# MCU_STM32F446RE.net
KiCad netlist of a schematic drawn in Altium Designer
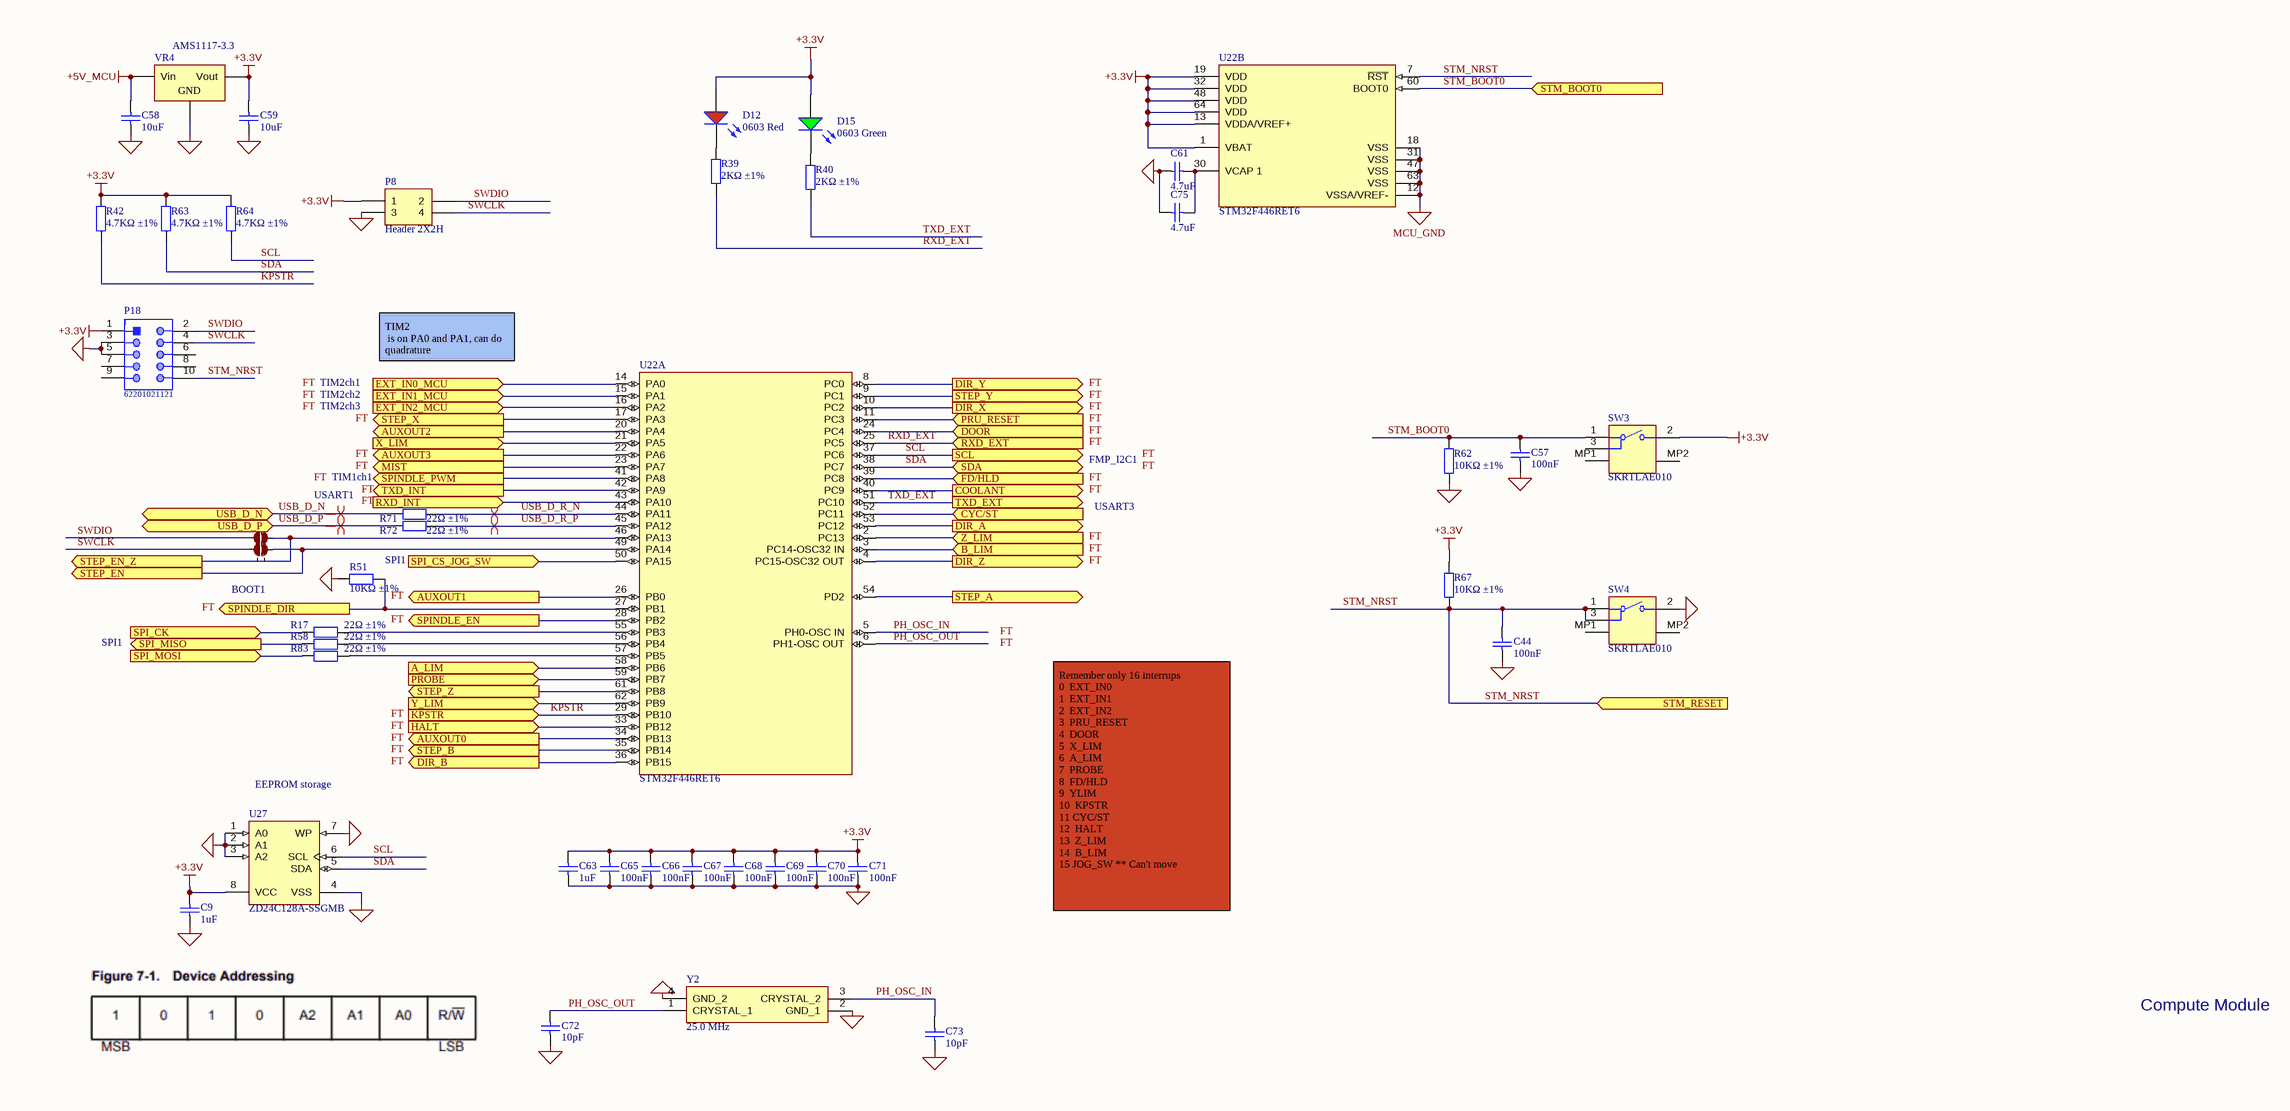
[diagram p0: MCU_STM32F446RE.SchDoc]

(export (version "E")
  (design (tool "Eeschema 10.0.6"))
  (components
    (comp (ref "C9")
      (value "1uF")
      (footprint "0603_C")
      (description "Chip capacitors")
      (fields
        (field (name "MANUFACTURER") "Samsung Electro-Mechanics")
        (field (name "PARTNUMBER") "CL10A105KB8NNNC")
      )
      (libsource (lib "Cap") (part "0603 1uF (105) 10% 50V"))
    )
    (comp (ref "C44")
      (value "100nF")
      (footprint "0603_C")
      (description "Chip capacitors")
      (fields (field (name "MANUFACTURER") "YAGEO") (field (name "PARTNUMBER") "CC0603KRX7R9BB104"))
      (libsource (lib "Cap") (part "0603 100nF (104) 10% 50V"))
    )
    (comp (ref "C57")
      (value "100nF")
      (footprint "0603_C")
      (description "Chip capacitors")
      (fields (field (name "MANUFACTURER") "YAGEO") (field (name "PARTNUMBER") "CC0603KRX7R9BB104"))
      (libsource (lib "Cap") (part "0603 100nF (104) 10% 50V"))
    )
    (comp (ref "C58")
      (value "10uF")
      (footprint "1206_C")
      (description "Chip capacitors")
      (fields
        (field (name "MANUFACTURER") "Samsung Electro-Mechanics")
        (field (name "PARTNUMBER") "CL31A106KBHNNNE")
      )
      (libsource (lib "Cap") (part "1206 10uF (106) 10% 50V"))
    )
    (comp (ref "C59")
      (value "10uF")
      (footprint "1206_C")
      (description "Chip capacitors")
      (fields
        (field (name "MANUFACTURER") "Samsung Electro-Mechanics")
        (field (name "PARTNUMBER") "CL31A106KBHNNNE")
      )
      (libsource (lib "Cap") (part "1206 10uF (106) 10% 50V"))
    )
    (comp (ref "C61")
      (value "4.7uF")
      (footprint "0603_C")
      (description "Chip capacitors")
      (fields
        (field (name "MANUFACTURER") "Samsung Electro-Mechanics")
        (field (name "PARTNUMBER") "CL10A475KO8NNNC")
      )
      (libsource (lib "Cap") (part "0603 4.7uF (475) 10% 16V"))
    )
    (comp (ref "C63")
      (value "1uF")
      (footprint "0603_C")
      (description "Chip capacitors")
      (fields
        (field (name "MANUFACTURER") "Samsung Electro-Mechanics")
        (field (name "PARTNUMBER") "CL10A105KB8NNNC")
      )
      (libsource (lib "Cap") (part "0603 1uF (105) 10% 50V"))
    )
    (comp (ref "C65")
      (value "100nF")
      (footprint "0603_C")
      (description "Chip capacitors")
      (fields (field (name "MANUFACTURER") "YAGEO") (field (name "PARTNUMBER") "CC0603KRX7R9BB104"))
      (libsource (lib "Cap") (part "0603 100nF (104) 10% 50V"))
    )
    (comp (ref "C66")
      (value "100nF")
      (footprint "0603_C")
      (description "Chip capacitors")
      (fields (field (name "MANUFACTURER") "YAGEO") (field (name "PARTNUMBER") "CC0603KRX7R9BB104"))
      (libsource (lib "Cap") (part "0603 100nF (104) 10% 50V"))
    )
    (comp (ref "C67")
      (value "100nF")
      (footprint "0603_C")
      (description "Chip capacitors")
      (fields (field (name "MANUFACTURER") "YAGEO") (field (name "PARTNUMBER") "CC0603KRX7R9BB104"))
      (libsource (lib "Cap") (part "0603 100nF (104) 10% 50V"))
    )
    (comp (ref "C68")
      (value "100nF")
      (footprint "0603_C")
      (description "Chip capacitors")
      (fields (field (name "MANUFACTURER") "YAGEO") (field (name "PARTNUMBER") "CC0603KRX7R9BB104"))
      (libsource (lib "Cap") (part "0603 100nF (104) 10% 50V"))
    )
    (comp (ref "C69")
      (value "100nF")
      (footprint "0603_C")
      (description "Chip capacitors")
      (fields (field (name "MANUFACTURER") "YAGEO") (field (name "PARTNUMBER") "CC0603KRX7R9BB104"))
      (libsource (lib "Cap") (part "0603 100nF (104) 10% 50V"))
    )
    (comp (ref "C70")
      (value "100nF")
      (footprint "0603_C")
      (description "Chip capacitors")
      (fields (field (name "MANUFACTURER") "YAGEO") (field (name "PARTNUMBER") "CC0603KRX7R9BB104"))
      (libsource (lib "Cap") (part "0603 100nF (104) 10% 50V"))
    )
    (comp (ref "C71")
      (value "100nF")
      (footprint "0603_C")
      (description "Chip capacitors")
      (fields (field (name "MANUFACTURER") "YAGEO") (field (name "PARTNUMBER") "CC0603KRX7R9BB104"))
      (libsource (lib "Cap") (part "0603 100nF (104) 10% 50V"))
    )
    (comp (ref "C72")
      (value "10pF")
      (footprint "0603_C")
      (description "Chip capacitors")
      (fields
        (field (name "MANUFACTURER") "Samsung Electro-Mechanics")
        (field (name "PARTNUMBER") "CL10C100JB8NNNC")
      )
      (libsource (lib "Cap") (part "0603 10pF (100) 5% 50V"))
    )
    (comp (ref "C73")
      (value "10pF")
      (footprint "0603_C")
      (description "Chip capacitors")
      (fields
        (field (name "MANUFACTURER") "Samsung Electro-Mechanics")
        (field (name "PARTNUMBER") "CL10C100JB8NNNC")
      )
      (libsource (lib "Cap") (part "0603 10pF (100) 5% 50V"))
    )
    (comp (ref "C75")
      (value "4.7uF")
      (footprint "0603_C")
      (description "Chip capacitors")
      (fields
        (field (name "MANUFACTURER") "Samsung Electro-Mechanics")
        (field (name "PARTNUMBER") "CL10A475KO8NNNC")
      )
      (libsource (lib "Cap") (part "0603 4.7uF (475) 10% 16V"))
    )
    (comp (ref "D12")
      (value "0603 Red")
      (footprint "0603_LED_S1")
      (description "LED")
      (libsource (lib "LED") (part "0603 LED Red"))
    )
    (comp (ref "D15")
      (value "0603 Green")
      (footprint "0603_LED_S1")
      (description "LED")
      (libsource (lib "LED") (part "0603 LED Green"))
    )
    (comp (ref "J10")
      (value "2 way net solder junction - Normally Open")
      (footprint "2waySolder_NO")
      (libsource (lib "PrintNC_GRBLHAL_Breakout") (part "2waySolderNO"))
    )
    (comp (ref "J11")
      (value "2 way net solder junction - Normally Open")
      (footprint "2waySolder_NO")
      (libsource (lib "PrintNC_GRBLHAL_Breakout") (part "2waySolderNO"))
    )
    (comp (ref "P8")
      (value "Header 2X2H")
      (footprint "HDR2X2H")
      (description "Header, 2-Pin, Dual row, Right Angle")
      (fields (field (name "PUBLISHER") "Altium Limited"))
      (libsource (lib "Miscellaneous Connectors") (part "Header 2X2H"))
    )
    (comp (ref "P18")
      (value "62201021121")
      (footprint "62201021121")
      (description "THT Vertical Pin Header WR-PHD, Pitch 1.27 mm, Dual Row, 10 pins")
      (fields (field (name "MANUFACTURER") "Wurth Elektronik") (field (name "PUBLISHER") "WurthElektronik"))
      (libsource (lib "Altium Content Vault") (part "WE-CN-2P-M-R10"))
    )
    (comp (ref "R17")
      (value "22Ω ±1%")
      (footprint "0603_R")
      (description "Chip resistor")
      (fields (field (name "MANUFACTURER") "Uniroyal Elec") (field (name "PARTNUMBER") "0603WAF220JT5E"))
      (libsource (lib "RES") (part "0603 22R (22R0) 1%"))
    )
    (comp (ref "R39")
      (value "2KΩ ±1%")
      (footprint "0603_R")
      (description "Chip resistor")
      (fields (field (name "MANUFACTURER") "Uniroyal Elec") (field (name "PARTNUMBER") "0603WAF2001T5E"))
      (libsource (lib "RES") (part "0603 2K (2001) 1%"))
    )
    (comp (ref "R40")
      (value "2KΩ ±1%")
      (footprint "0603_R")
      (description "Chip resistor")
      (fields (field (name "MANUFACTURER") "Uniroyal Elec") (field (name "PARTNUMBER") "0603WAF2001T5E"))
      (libsource (lib "RES") (part "0603 2K (2001) 1%"))
    )
    (comp (ref "R42")
      (value "4.7KΩ ±1%")
      (footprint "0603_R")
      (description "Chip resistor")
      (fields (field (name "MANUFACTURER") "Uniroyal Elec") (field (name "PARTNUMBER") "0603WAF4701T5E"))
      (libsource (lib "RES") (part "0603 4.7K (4701) 1%"))
    )
    (comp (ref "R51")
      (value "10KΩ ±1%")
      (footprint "0603_R")
      (description "Chip resistor")
      (fields (field (name "MANUFACTURER") "Uniroyal Elec") (field (name "PARTNUMBER") "0603WAF1002T5E"))
      (libsource (lib "RES") (part "0603 10K (1002) 1%"))
    )
    (comp (ref "R58")
      (value "22Ω ±1%")
      (footprint "0603_R")
      (description "Chip resistor")
      (fields (field (name "MANUFACTURER") "Uniroyal Elec") (field (name "PARTNUMBER") "0603WAF220JT5E"))
      (libsource (lib "RES") (part "0603 22R (22R0) 1%"))
    )
    (comp (ref "R62")
      (value "10KΩ ±1%")
      (footprint "0603_R")
      (description "Chip resistor")
      (fields (field (name "MANUFACTURER") "Uniroyal Elec") (field (name "PARTNUMBER") "0603WAF1002T5E"))
      (libsource (lib "") (part "0603 10K (1002) 1%_1"))
    )
    (comp (ref "R63")
      (value "4.7KΩ ±1%")
      (footprint "0603_R")
      (description "Chip resistor")
      (fields (field (name "MANUFACTURER") "Uniroyal Elec") (field (name "PARTNUMBER") "0603WAF4701T5E"))
      (libsource (lib "RES") (part "0603 4.7K (4701) 1%"))
    )
    (comp (ref "R64")
      (value "4.7KΩ ±1%")
      (footprint "0603_R")
      (description "Chip resistor")
      (fields (field (name "MANUFACTURER") "Uniroyal Elec") (field (name "PARTNUMBER") "0603WAF4701T5E"))
      (libsource (lib "RES") (part "0603 4.7K (4701) 1%"))
    )
    (comp (ref "R67")
      (value "10KΩ ±1%")
      (footprint "0603_R")
      (description "Chip resistor")
      (fields (field (name "MANUFACTURER") "Uniroyal Elec") (field (name "PARTNUMBER") "0603WAF1002T5E"))
      (libsource (lib "") (part "0603 10K (1002) 1%_1"))
    )
    (comp (ref "R71")
      (value "22Ω ±1%")
      (footprint "0603_R")
      (description "Chip resistor")
      (fields (field (name "MANUFACTURER") "Uniroyal Elec") (field (name "PARTNUMBER") "0603WAF220JT5E"))
      (libsource (lib "RES") (part "0603 22R (22R0) 1%"))
    )
    (comp (ref "R72")
      (value "22Ω ±1%")
      (footprint "0603_R")
      (description "Chip resistor")
      (fields (field (name "MANUFACTURER") "Uniroyal Elec") (field (name "PARTNUMBER") "0603WAF220JT5E"))
      (libsource (lib "RES") (part "0603 22R (22R0) 1%"))
    )
    (comp (ref "R83")
      (value "22Ω ±1%")
      (footprint "0603_R")
      (description "Chip resistor")
      (fields (field (name "MANUFACTURER") "Uniroyal Elec") (field (name "PARTNUMBER") "0603WAF220JT5E"))
      (libsource (lib "RES") (part "0603 22R (22R0) 1%"))
    )
    (comp (ref "SW3")
      (value "SKRTLAE010")
      (footprint "ALPS-SKRTLAE010_V")
      (description "Side Push Type, 250 V, -40 to 90 degC, 3-Pin SMD, RoHS, Tape and Reel")
      (fields (field (name "MANUFACTURER") "ALPS"))
      (libsource (lib "Altium Content Vault") (part "SW_SPST-3_A"))
    )
    (comp (ref "SW4")
      (value "SKRTLAE010")
      (footprint "ALPS-SKRTLAE010_V")
      (description "Side Push Type, 250 V, -40 to 90 degC, 3-Pin SMD, RoHS, Tape and Reel")
      (fields (field (name "MANUFACTURER") "ALPS"))
      (libsource (lib "Altium Content Vault") (part "SW_SPST-3_A"))
    )
    (comp (ref "U22")
      (value "STM32F446RET6")
      (footprint "FP-LQFP64-5W-IPC_B")
      (description "IC MCU 32BIT 512KB FLASH 64LQFP")
      (fields
        (field (name "OCTOPART") "https://octopart.com/stm32f446ret6-stmicroelectronics-52642920")
        (field (name "MANUFACTURER") "STMicroelectronics")
      )
      (libsource (lib "Universal_CNC_Breakout") (part "STM32F446RET6"))
    )
    (comp (ref "U27")
      (value "ZD24C128A-SSGMB")
      (footprint "SOIC-SN8_L")
      (description "IC EEPROM 128KBIT I2C 8SOIC")
      (libsource (lib "PrintNC_GRBLHAL_Breakout") (part "MEM-SEEPROM-34AA02-IL8"))
    )
    (comp (ref "VR4")
      (value "AMS1117-3.3")
      (footprint "SOT-223")
      (description "Vout=3.3V 1A 72dB@(120Hz) (LDO)")
      (libsource (lib "LDO") (part "SOT-223 AMS1117-3.3"))
    )
    (comp (ref "Y2")
      (value "25.0 MHz")
      (footprint "SamacSys:YSX321SL")
      (description "Crystal or Oscillator")
      (fields (field (name "MANUFACTURER_PART_NUMBER") "X322525MSB4SI"))
      (libsource (lib "*") (part "YSX321SL"))
    )
  )
  (nets
    (net (code "1") (name "+3.3V") (class "Default")
      (node (ref "C59") (pin "2") (pinfunction "2_2") (pintype "passive"))
      (node (ref "C63") (pin "2") (pinfunction "2_2") (pintype "passive"))
      (node (ref "C65") (pin "2") (pinfunction "2_2") (pintype "passive"))
      (node (ref "C66") (pin "2") (pinfunction "2_2") (pintype "passive"))
      (node (ref "C67") (pin "2") (pinfunction "2_2") (pintype "passive"))
      (node (ref "C68") (pin "2") (pinfunction "2_2") (pintype "passive"))
      (node (ref "C69") (pin "2") (pinfunction "2_2") (pintype "passive"))
      (node (ref "C70") (pin "2") (pinfunction "2_2") (pintype "passive"))
      (node (ref "C71") (pin "2") (pinfunction "2_2") (pintype "passive"))
      (node (ref "C9") (pin "2") (pinfunction "2_2") (pintype "passive"))
      (node (ref "D12") (pin "A") (pinfunction "A_A") (pintype "passive"))
      (node (ref "D15") (pin "A") (pinfunction "A_A") (pintype "passive"))
      (node (ref "P18") (pin "1") (pinfunction "1_1") (pintype "passive"))
      (node (ref "P8") (pin "1") (pinfunction "1_1") (pintype "passive"))
      (node (ref "R42") (pin "2") (pinfunction "2_2") (pintype "passive"))
      (node (ref "R63") (pin "2") (pinfunction "2_2") (pintype "passive"))
      (node (ref "R64") (pin "2") (pinfunction "2_2") (pintype "passive"))
      (node (ref "R67") (pin "1") (pinfunction "1_1") (pintype "passive"))
      (node (ref "SW3") (pin "2") (pinfunction "2_2") (pintype "passive"))
      (node (ref "U22") (pin "1") (pinfunction "VBAT_1") (pintype "power_in"))
      (node (ref "U22") (pin "13") (pinfunction "VDDA/VREF+_13") (pintype "power_in"))
      (node (ref "U22") (pin "19") (pinfunction "VDD_19") (pintype "power_in"))
      (node (ref "U22") (pin "32") (pinfunction "VDD_32") (pintype "power_in"))
      (node (ref "U22") (pin "48") (pinfunction "VDD_48") (pintype "power_in"))
      (node (ref "U22") (pin "64") (pinfunction "VDD_64") (pintype "power_in"))
      (node (ref "U27") (pin "8") (pinfunction "VCC_8") (pintype "power_in"))
      (node (ref "VR4") (pin "2") (pinfunction "Vout_2") (pintype "passive"))
    )
    (net (code "2") (name "+5V_MCU") (class "Default")
      (node (ref "C58") (pin "2") (pinfunction "2_2") (pintype "passive"))
      (node (ref "VR4") (pin "3") (pinfunction "Vin_3") (pintype "passive"))
    )
    (net (code "3") (name "/AUXOUT0") (class "Default")
      (node (ref "U22") (pin "34") (pinfunction "PB13_34") (pintype "bidirectional"))
    )
    (net (code "4") (name "/AUXOUT1") (class "Default")
      (node (ref "U22") (pin "26") (pinfunction "PB0_26") (pintype "bidirectional"))
    )
    (net (code "5") (name "/AUXOUT2") (class "Default")
      (node (ref "U22") (pin "20") (pinfunction "PA4_20") (pintype "bidirectional"))
    )
    (net (code "6") (name "/AUXOUT3") (class "Default")
      (node (ref "U22") (pin "22") (pinfunction "PA6_22") (pintype "bidirectional"))
    )
    (net (code "7") (name "/A_LIM") (class "Default")
      (node (ref "U22") (pin "58") (pinfunction "PB6_58") (pintype "bidirectional"))
    )
    (net (code "8") (name "/B_LIM") (class "Default")
      (node (ref "U22") (pin "3") (pinfunction "PC14-OSC32_IN_3") (pintype "bidirectional"))
    )
    (net (code "9") (name "/COOLANT") (class "Default")
      (node (ref "U22") (pin "40") (pinfunction "PC9_40") (pintype "bidirectional"))
    )
    (net (code "10") (name "/CYC{slash}ST") (class "Default")
      (node (ref "U22") (pin "52") (pinfunction "PC11_52") (pintype "bidirectional"))
    )
    (net (code "11") (name "/DIR_A") (class "Default")
      (node (ref "U22") (pin "53") (pinfunction "PC12_53") (pintype "bidirectional"))
    )
    (net (code "12") (name "/DIR_B") (class "Default")
      (node (ref "U22") (pin "36") (pinfunction "PB15_36") (pintype "bidirectional"))
    )
    (net (code "13") (name "/DIR_X") (class "Default")
      (node (ref "U22") (pin "10") (pinfunction "PC2_10") (pintype "bidirectional"))
    )
    (net (code "14") (name "/DIR_Y") (class "Default")
      (node (ref "U22") (pin "8") (pinfunction "PC0_8") (pintype "bidirectional"))
    )
    (net (code "15") (name "/DIR_Z") (class "Default")
      (node (ref "U22") (pin "4") (pinfunction "PC15-OSC32_OUT_4") (pintype "bidirectional"))
    )
    (net (code "16") (name "/DOOR") (class "Default")
      (node (ref "U22") (pin "24") (pinfunction "PC4_24") (pintype "bidirectional"))
    )
    (net (code "17") (name "/EXT_IN0_MCU") (class "Default")
      (node (ref "U22") (pin "14") (pinfunction "PA0_14") (pintype "bidirectional"))
    )
    (net (code "18") (name "/EXT_IN1_MCU") (class "Default")
      (node (ref "U22") (pin "15") (pinfunction "PA1_15") (pintype "bidirectional"))
    )
    (net (code "19") (name "/EXT_IN2_MCU") (class "Default")
      (node (ref "U22") (pin "16") (pinfunction "PA2_16") (pintype "bidirectional"))
    )
    (net (code "20") (name "/FD{slash}HLD") (class "Default")
      (node (ref "U22") (pin "39") (pinfunction "PC8_39") (pintype "bidirectional"))
    )
    (net (code "21") (name "/HALT") (class "Default")
      (node (ref "U22") (pin "33") (pinfunction "PB12_33") (pintype "bidirectional"))
    )
    (net (code "22") (name "/KPSTR") (class "Default")
      (node (ref "R42") (pin "1") (pinfunction "1_1") (pintype "passive"))
      (node (ref "U22") (pin "29") (pinfunction "PB10_29") (pintype "bidirectional"))
    )
    (net (code "23") (name "/MIST") (class "Default")
      (node (ref "U22") (pin "23") (pinfunction "PA7_23") (pintype "bidirectional"))
    )
    (net (code "24") (name "/PH_OSC_IN") (class "Default")
      (node (ref "C73") (pin "2") (pinfunction "2_2") (pintype "passive"))
      (node (ref "U22") (pin "5") (pinfunction "PH0-OSC_IN_5") (pintype "bidirectional"))
      (node (ref "Y2") (pin "3") (pinfunction "CRYSTAL_2_3") (pintype "passive"))
    )
    (net (code "25") (name "/PH_OSC_OUT") (class "Default")
      (node (ref "C72") (pin "2") (pinfunction "2_2") (pintype "passive"))
      (node (ref "U22") (pin "6") (pinfunction "PH1-OSC_OUT_6") (pintype "bidirectional"))
      (node (ref "Y2") (pin "1") (pinfunction "CRYSTAL_1_1") (pintype "passive"))
    )
    (net (code "26") (name "/PROBE") (class "Default")
      (node (ref "U22") (pin "59") (pinfunction "PB7_59") (pintype "bidirectional"))
    )
    (net (code "27") (name "/PRU_RESET") (class "Default")
      (node (ref "U22") (pin "11") (pinfunction "PC3_11") (pintype "bidirectional"))
    )
    (net (code "28") (name "/RXD_EXT") (class "Default")
      (node (ref "R39") (pin "1") (pinfunction "1_1") (pintype "passive"))
      (node (ref "U22") (pin "25") (pinfunction "PC5_25") (pintype "bidirectional"))
    )
    (net (code "29") (name "/RXD_INT") (class "Default")
      (node (ref "U22") (pin "43") (pinfunction "PA10_43") (pintype "bidirectional"))
    )
    (net (code "30") (name "/SCL") (class "Default")
      (node (ref "R64") (pin "1") (pinfunction "1_1") (pintype "passive"))
      (node (ref "U22") (pin "37") (pinfunction "PC6_37") (pintype "bidirectional"))
      (node (ref "U27") (pin "6") (pinfunction "SCL_6") (pintype "input"))
    )
    (net (code "31") (name "/SDA") (class "Default")
      (node (ref "R63") (pin "1") (pinfunction "1_1") (pintype "passive"))
      (node (ref "U22") (pin "38") (pinfunction "PC7_38") (pintype "bidirectional"))
      (node (ref "U27") (pin "5") (pinfunction "SDA_5") (pintype "bidirectional"))
    )
    (net (code "32") (name "/SPINDLE_DIR") (class "Default")
      (node (ref "R51") (pin "2") (pinfunction "2_2") (pintype "passive"))
      (node (ref "U22") (pin "27") (pinfunction "PB1_27") (pintype "bidirectional"))
    )
    (net (code "33") (name "/SPINDLE_EN") (class "Default")
      (node (ref "U22") (pin "28") (pinfunction "PB2_28") (pintype "bidirectional"))
    )
    (net (code "34") (name "/SPINDLE_PWM") (class "Default")
      (node (ref "U22") (pin "41") (pinfunction "PA8_41") (pintype "bidirectional"))
    )
    (net (code "35") (name "/SPI_CK") (class "Default")
      (node (ref "R17") (pin "2") (pinfunction "2_2") (pintype "passive"))
    )
    (net (code "36") (name "/SPI_CS_JOG_SW") (class "Default")
      (node (ref "U22") (pin "50") (pinfunction "PA15_50") (pintype "bidirectional"))
    )
    (net (code "37") (name "/SPI_MISO") (class "Default")
      (node (ref "R58") (pin "2") (pinfunction "2_2") (pintype "passive"))
    )
    (net (code "38") (name "/SPI_MOSI") (class "Default")
      (node (ref "R83") (pin "2") (pinfunction "2_2") (pintype "passive"))
    )
    (net (code "39") (name "/STEP_A") (class "Default")
      (node (ref "U22") (pin "54") (pinfunction "PD2_54") (pintype "bidirectional"))
    )
    (net (code "40") (name "/STEP_B") (class "Default")
      (node (ref "U22") (pin "35") (pinfunction "PB14_35") (pintype "bidirectional"))
    )
    (net (code "41") (name "/STEP_EN") (class "Default")
      (node (ref "J11") (pin "2") (pinfunction "2_2") (pintype "passive"))
      (node (ref "U22") (pin "49") (pinfunction "PA14_49") (pintype "bidirectional"))
    )
    (net (code "42") (name "/STEP_EN_Z") (class "Default")
      (node (ref "J10") (pin "2") (pinfunction "2_2") (pintype "passive"))
      (node (ref "U22") (pin "46") (pinfunction "PA13_46") (pintype "bidirectional"))
    )
    (net (code "43") (name "/STEP_X") (class "Default")
      (node (ref "U22") (pin "17") (pinfunction "PA3_17") (pintype "bidirectional"))
    )
    (net (code "44") (name "/STEP_Y") (class "Default")
      (node (ref "U22") (pin "9") (pinfunction "PC1_9") (pintype "bidirectional"))
    )
    (net (code "45") (name "/STEP_Z") (class "Default")
      (node (ref "U22") (pin "61") (pinfunction "PB8_61") (pintype "bidirectional"))
    )
    (net (code "46") (name "/STM_BOOT0") (class "Default")
      (node (ref "C57") (pin "2") (pinfunction "2_2") (pintype "passive"))
      (node (ref "R62") (pin "1") (pinfunction "1_1") (pintype "passive"))
      (node (ref "SW3") (pin "1") (pinfunction "1_1") (pintype "passive"))
      (node (ref "U22") (pin "60") (pinfunction "BOOT0_60") (pintype "input"))
    )
    (net (code "47") (name "/STM_NRST") (class "Default")
      (node (ref "C44") (pin "2") (pinfunction "2_2") (pintype "passive"))
      (node (ref "P18") (pin "10") (pinfunction "10_10") (pintype "passive"))
      (node (ref "R67") (pin "2") (pinfunction "2_2") (pintype "passive"))
      (node (ref "SW4") (pin "1") (pinfunction "1_1") (pintype "passive"))
      (node (ref "SW4") (pin "3") (pinfunction "3_3") (pintype "passive"))
      (node (ref "U22") (pin "7") (pinfunction "~{RST}_7") (pintype "input"))
    )
    (net (code "48") (name "/SWCLK") (class "Default")
      (node (ref "J11") (pin "1") (pinfunction "1_1") (pintype "passive"))
      (node (ref "P18") (pin "4") (pinfunction "4_4") (pintype "passive"))
      (node (ref "P8") (pin "4") (pinfunction "4_4") (pintype "passive"))
    )
    (net (code "49") (name "/SWDIO") (class "Default")
      (node (ref "J10") (pin "1") (pinfunction "1_1") (pintype "passive"))
      (node (ref "P18") (pin "2") (pinfunction "2_2") (pintype "passive"))
      (node (ref "P8") (pin "2") (pinfunction "2_2") (pintype "passive"))
    )
    (net (code "50") (name "/TXD_EXT") (class "Default")
      (node (ref "R40") (pin "1") (pinfunction "1_1") (pintype "passive"))
      (node (ref "U22") (pin "51") (pinfunction "PC10_51") (pintype "bidirectional"))
    )
    (net (code "51") (name "/TXD_INT") (class "Default")
      (node (ref "U22") (pin "42") (pinfunction "PA9_42") (pintype "bidirectional"))
    )
    (net (code "52") (name "/USB_D_N") (class "Default")
      (node (ref "R71") (pin "2") (pinfunction "2_2") (pintype "passive"))
    )
    (net (code "53") (name "/USB_D_P") (class "Default")
      (node (ref "R72") (pin "2") (pinfunction "2_2") (pintype "passive"))
    )
    (net (code "54") (name "/USB_D_R_N") (class "Default")
      (node (ref "R71") (pin "1") (pinfunction "1_1") (pintype "passive"))
      (node (ref "U22") (pin "44") (pinfunction "PA11_44") (pintype "bidirectional"))
    )
    (net (code "55") (name "/USB_D_R_P") (class "Default")
      (node (ref "R72") (pin "1") (pinfunction "1_1") (pintype "passive"))
      (node (ref "U22") (pin "45") (pinfunction "PA12_45") (pintype "bidirectional"))
    )
    (net (code "56") (name "/X_LIM") (class "Default")
      (node (ref "U22") (pin "21") (pinfunction "PA5_21") (pintype "bidirectional"))
    )
    (net (code "57") (name "/Y_LIM") (class "Default")
      (node (ref "U22") (pin "62") (pinfunction "PB9_62") (pintype "bidirectional"))
    )
    (net (code "58") (name "/Z_LIM") (class "Default")
      (node (ref "U22") (pin "2") (pinfunction "PC13_2") (pintype "bidirectional"))
    )
    (net (code "59") (name "MCU_GND") (class "Default")
      (node (ref "C44") (pin "1") (pinfunction "1_1") (pintype "passive"))
      (node (ref "C57") (pin "1") (pinfunction "1_1") (pintype "passive"))
      (node (ref "C58") (pin "1") (pinfunction "1_1") (pintype "passive"))
      (node (ref "C59") (pin "1") (pinfunction "1_1") (pintype "passive"))
      (node (ref "C61") (pin "1") (pinfunction "1_1") (pintype "passive"))
      (node (ref "C63") (pin "1") (pinfunction "1_1") (pintype "passive"))
      (node (ref "C65") (pin "1") (pinfunction "1_1") (pintype "passive"))
      (node (ref "C66") (pin "1") (pinfunction "1_1") (pintype "passive"))
      (node (ref "C67") (pin "1") (pinfunction "1_1") (pintype "passive"))
      (node (ref "C68") (pin "1") (pinfunction "1_1") (pintype "passive"))
      (node (ref "C69") (pin "1") (pinfunction "1_1") (pintype "passive"))
      (node (ref "C70") (pin "1") (pinfunction "1_1") (pintype "passive"))
      (node (ref "C71") (pin "1") (pinfunction "1_1") (pintype "passive"))
      (node (ref "C72") (pin "1") (pinfunction "1_1") (pintype "passive"))
      (node (ref "C73") (pin "1") (pinfunction "1_1") (pintype "passive"))
      (node (ref "C75") (pin "1") (pinfunction "1_1") (pintype "passive"))
      (node (ref "C9") (pin "1") (pinfunction "1_1") (pintype "passive"))
      (node (ref "P18") (pin "3") (pinfunction "3_3") (pintype "passive"))
      (node (ref "P18") (pin "5") (pinfunction "5_5") (pintype "passive"))
      (node (ref "P8") (pin "3") (pinfunction "3_3") (pintype "passive"))
      (node (ref "R51") (pin "1") (pinfunction "1_1") (pintype "passive"))
      (node (ref "R62") (pin "2") (pinfunction "2_2") (pintype "passive"))
      (node (ref "SW4") (pin "2") (pinfunction "2_2") (pintype "passive"))
      (node (ref "U22") (pin "12") (pinfunction "VSSA/VREF-_12") (pintype "power_in"))
      (node (ref "U22") (pin "18") (pinfunction "VSS_18") (pintype "power_in"))
      (node (ref "U22") (pin "31") (pinfunction "VSS_31") (pintype "power_in"))
      (node (ref "U22") (pin "47") (pinfunction "VSS_47") (pintype "power_in"))
      (node (ref "U22") (pin "63") (pinfunction "VSS_63") (pintype "power_in"))
      (node (ref "U27") (pin "1") (pinfunction "A0_1") (pintype "input"))
      (node (ref "U27") (pin "2") (pinfunction "A1_2") (pintype "input"))
      (node (ref "U27") (pin "3") (pinfunction "A2_3") (pintype "input"))
      (node (ref "U27") (pin "4") (pinfunction "VSS_4") (pintype "power_in"))
      (node (ref "U27") (pin "7") (pinfunction "WP_7") (pintype "input"))
      (node (ref "VR4") (pin "1") (pinfunction "GND_1") (pintype "passive"))
      (node (ref "Y2") (pin "2") (pinfunction "GND_1_2") (pintype "passive"))
      (node (ref "Y2") (pin "4") (pinfunction "GND_2_4") (pintype "passive"))
    )
    (net (code "60") (name "Net-(D12-PadK)") (class "Default")
      (node (ref "D12") (pin "K") (pinfunction "K_K") (pintype "passive"))
      (node (ref "R39") (pin "2") (pinfunction "2_2") (pintype "passive"))
    )
    (net (code "61") (name "Net-(D15-PadK)") (class "Default")
      (node (ref "D15") (pin "K") (pinfunction "K_K") (pintype "passive"))
      (node (ref "R40") (pin "2") (pinfunction "2_2") (pintype "passive"))
    )
    (net (code "62") (name "Net-(U22A-PB3)") (class "Default")
      (node (ref "R17") (pin "1") (pinfunction "1_1") (pintype "passive"))
      (node (ref "U22") (pin "55") (pinfunction "PB3_55") (pintype "bidirectional"))
    )
    (net (code "63") (name "Net-(U22A-PB4)") (class "Default")
      (node (ref "R58") (pin "1") (pinfunction "1_1") (pintype "passive"))
      (node (ref "U22") (pin "56") (pinfunction "PB4_56") (pintype "bidirectional"))
    )
    (net (code "64") (name "Net-(U22A-PB5)") (class "Default")
      (node (ref "R83") (pin "1") (pinfunction "1_1") (pintype "passive"))
      (node (ref "U22") (pin "57") (pinfunction "PB5_57") (pintype "bidirectional"))
    )
    (net (code "65") (name "Net-(U22B-VCAP_1)") (class "Default")
      (node (ref "C61") (pin "2") (pinfunction "2_2") (pintype "passive"))
      (node (ref "C75") (pin "2") (pinfunction "2_2") (pintype "passive"))
      (node (ref "U22") (pin "30") (pinfunction "VCAP_1_30") (pintype "power_in"))
    )
    (net (code "66") (name "unconnected-(P18-Pad6)") (class "Default")
      (node (ref "P18") (pin "6") (pinfunction "6_6") (pintype "passive"))
    )
    (net (code "67") (name "unconnected-(P18-Pad7)") (class "Default")
      (node (ref "P18") (pin "7") (pinfunction "7_7") (pintype "passive"))
    )
    (net (code "68") (name "unconnected-(P18-Pad8)") (class "Default")
      (node (ref "P18") (pin "8") (pinfunction "8_8") (pintype "passive"))
    )
    (net (code "69") (name "unconnected-(P18-Pad9)") (class "Default")
      (node (ref "P18") (pin "9") (pinfunction "9_9") (pintype "passive"))
    )
    (net (code "70") (name "unconnected-(SW3-Pad3)") (class "Default")
      (node (ref "SW3") (pin "3") (pinfunction "3_3") (pintype "passive"))
    )
    (net (code "71") (name "unconnected-(SW3-PadMP1)") (class "Default")
      (node (ref "SW3") (pin "MP1") (pinfunction "MP1_MP1") (pintype "passive"))
    )
    (net (code "72") (name "unconnected-(SW3-PadMP2)") (class "Default")
      (node (ref "SW3") (pin "MP2") (pinfunction "MP2_MP2") (pintype "passive"))
    )
    (net (code "73") (name "unconnected-(SW4-PadMP1)") (class "Default")
      (node (ref "SW4") (pin "MP1") (pinfunction "MP1_MP1") (pintype "passive"))
    )
    (net (code "74") (name "unconnected-(SW4-PadMP2)") (class "Default")
      (node (ref "SW4") (pin "MP2") (pinfunction "MP2_MP2") (pintype "passive"))
    )
  )
)
